# power_usb.net
KiCad netlist of a schematic drawn in Altium Designer
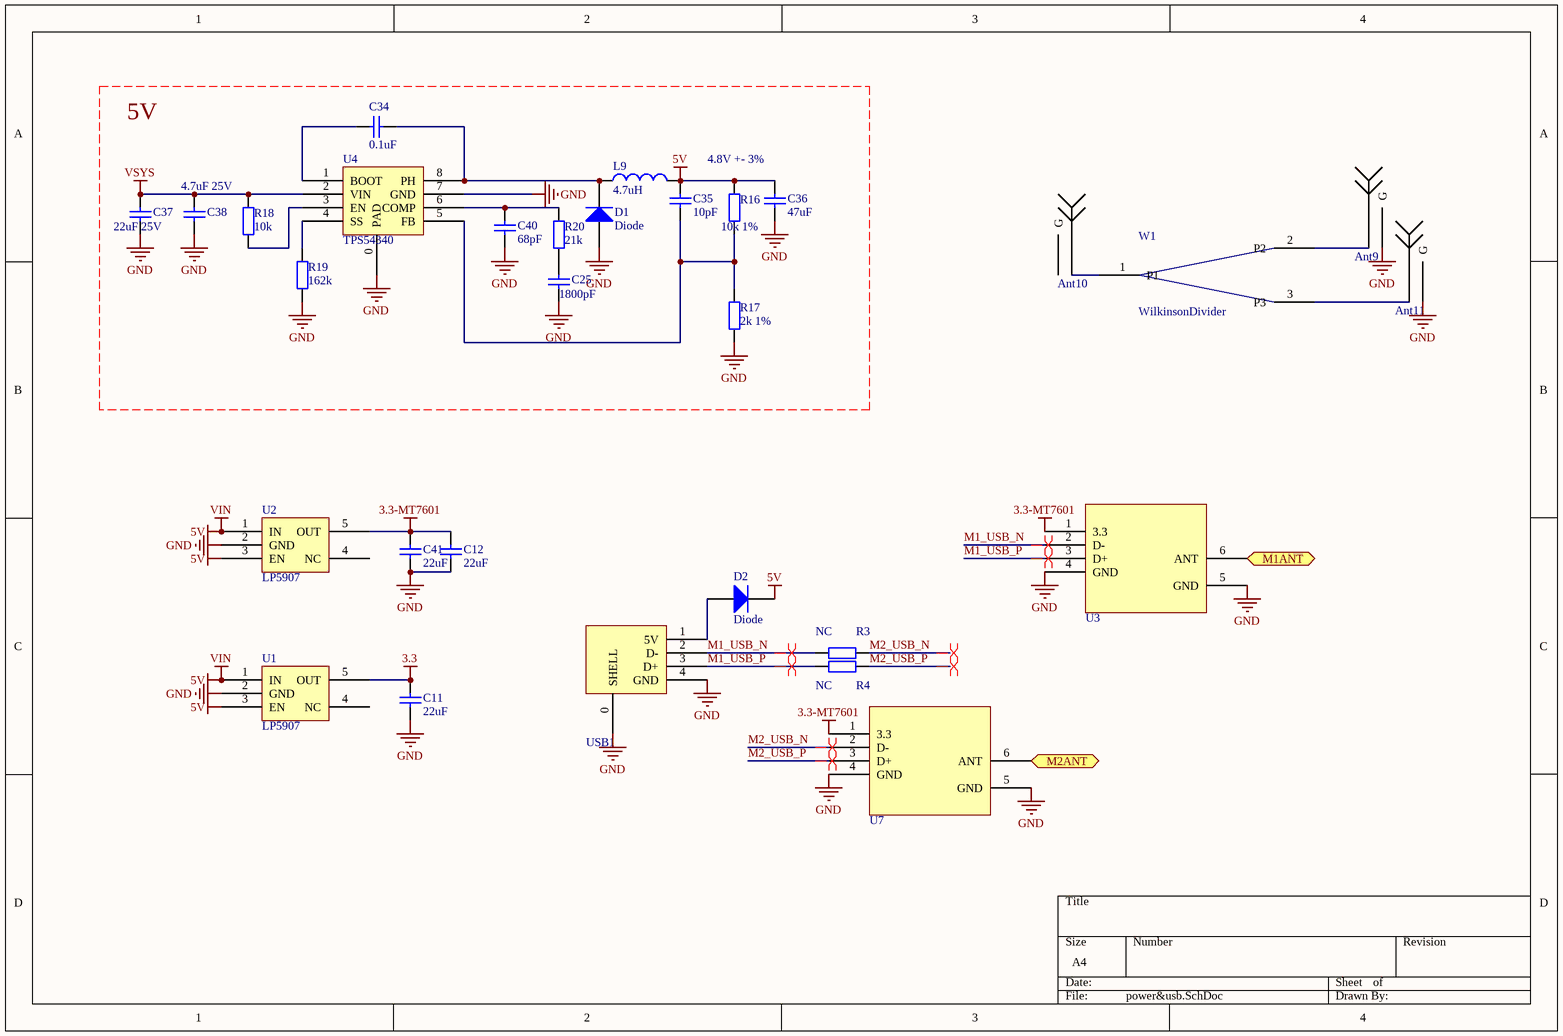
[diagram p0: power&usb.SchDoc]

(export (version "E")
  (design (tool "Eeschema 10.0.6"))
  (components
    (comp (ref "Ant9") (value "Antenna") (footprint "SMA-2") (libsource (lib "RTC6705") (part "Antenna")))
    (comp (ref "Ant10") (value "Antenna") (footprint "SMA-2") (libsource (lib "RTC6705") (part "Antenna")))
    (comp (ref "Ant11") (value "Antenna") (footprint "SMA-2") (libsource (lib "RTC6705") (part "Antenna")))
    (comp (ref "C11")
      (value "22uF")
      (footprint "0805")
      (description "Capacitor")
      (fields (field (name "Comment") "Cap") (field (name "PUBLISHER") "Altium Limited"))
      (libsource (lib "RTC6705") (part "Cap"))
    )
    (comp (ref "C12")
      (value "22uF")
      (footprint "0805")
      (description "Capacitor")
      (fields (field (name "Comment") "Cap") (field (name "PUBLISHER") "Altium Limited"))
      (libsource (lib "RTC6705") (part "Cap"))
    )
    (comp (ref "C25")
      (value "1800pF")
      (footprint "0402")
      (description "Capacitor")
      (fields (field (name "Comment") "Cap") (field (name "PUBLISHER") "Altium Limited"))
      (libsource (lib "RTC6705") (part "Cap"))
    )
    (comp (ref "C34")
      (value "0.1uF")
      (footprint "0402")
      (description "Capacitor")
      (fields (field (name "Comment") "Cap") (field (name "PUBLISHER") "Altium Limited"))
      (libsource (lib "RTC6705") (part "Cap"))
    )
    (comp (ref "C35")
      (value "10pF")
      (footprint "0402")
      (description "Capacitor")
      (fields (field (name "Comment") "Cap") (field (name "PUBLISHER") "Altium Limited"))
      (libsource (lib "RTC6705") (part "Cap"))
    )
    (comp (ref "C36")
      (value "47uF")
      (footprint "1210")
      (description "Capacitor")
      (fields (field (name "Comment") "Cap") (field (name "PUBLISHER") "Altium Limited"))
      (libsource (lib "RTC6705") (part "Cap"))
    )
    (comp (ref "C37")
      (value "22uF 25V")
      (footprint "1210")
      (description "Capacitor")
      (fields (field (name "Comment") "Cap") (field (name "PUBLISHER") "Altium Limited"))
      (libsource (lib "RTC6705") (part "Cap"))
    )
    (comp (ref "C38")
      (value "4.7uF 25V")
      (footprint "0805")
      (description "Capacitor")
      (fields (field (name "Comment") "Cap") (field (name "PUBLISHER") "Altium Limited"))
      (libsource (lib "RTC6705") (part "Cap"))
    )
    (comp (ref "C40")
      (value "68pF")
      (footprint "0402")
      (description "Capacitor")
      (fields (field (name "Comment") "Cap") (field (name "PUBLISHER") "Altium Limited"))
      (libsource (lib "RTC6705") (part "Cap"))
    )
    (comp (ref "C41")
      (value "22uF")
      (footprint "0805")
      (description "Capacitor")
      (fields (field (name "Comment") "Cap") (field (name "PUBLISHER") "Altium Limited"))
      (libsource (lib "RTC6705") (part "Cap"))
    )
    (comp (ref "D1")
      (value "Diode")
      (footprint "LC-SMB(DO-214AA)_S1")
      (description "Default Diode")
      (fields (field (name "PUBLISHER") "Altium Limited"))
      (libsource (lib "Miscellaneous Devices") (part "Diode"))
    )
    (comp (ref "D2")
      (value "Diode")
      (footprint "0805")
      (description "Default Diode")
      (fields (field (name "PUBLISHER") "Altium Limited"))
      (libsource (lib "Miscellaneous Devices") (part "Diode"))
    )
    (comp (ref "L9")
      (value "4.7uH")
      (footprint "L7022")
      (description "Inductor")
      (fields (field (name "PUBLISHER") "Altium Limited"))
      (libsource (lib "Miscellaneous Devices") (part "Inductor"))
    )
    (comp (ref "R3")
      (value "NC")
      (footprint "0402")
      (description "Resistor")
      (fields (field (name "Comment") "Res2") (field (name "PUBLISHER") "Altium Limited"))
      (libsource (lib "") (part "Res2_1"))
    )
    (comp (ref "R4")
      (value "NC")
      (footprint "0402")
      (description "Resistor")
      (fields (field (name "Comment") "Res2") (field (name "PUBLISHER") "Altium Limited"))
      (libsource (lib "") (part "Res2_1"))
    )
    (comp (ref "R16")
      (value "10k 1%")
      (footprint "0402")
      (description "Resistor")
      (fields (field (name "Comment") "Res2") (field (name "PUBLISHER") "Altium Limited"))
      (libsource (lib "RTC6705") (part "Res2"))
    )
    (comp (ref "R17")
      (value "2k 1%")
      (footprint "0402")
      (description "Resistor")
      (fields (field (name "Comment") "Res2") (field (name "PUBLISHER") "Altium Limited"))
      (libsource (lib "RTC6705") (part "Res2"))
    )
    (comp (ref "R18")
      (value "10k")
      (footprint "0402")
      (description "Resistor")
      (fields (field (name "Comment") "Res2") (field (name "PUBLISHER") "Altium Limited"))
      (libsource (lib "RTC6705") (part "Res2"))
    )
    (comp (ref "R19")
      (value "162k")
      (footprint "0402")
      (description "Resistor")
      (fields (field (name "Comment") "Res2") (field (name "PUBLISHER") "Altium Limited"))
      (libsource (lib "RTC6705") (part "Res2"))
    )
    (comp (ref "R20")
      (value "21k")
      (footprint "0402")
      (description "Resistor")
      (fields (field (name "Comment") "Res2") (field (name "PUBLISHER") "Altium Limited"))
      (libsource (lib "RTC6705") (part "Res2"))
    )
    (comp (ref "U1") (value "LP5907") (footprint "SOT23-5") (libsource (lib "RTC6705") (part "LP5907")))
    (comp (ref "U2") (value "LP5907") (footprint "SOT23-5") (libsource (lib "RTC6705") (part "LP5907")))
    (comp (ref "U3")
      (value "MT7601-Module")
      (footprint "MT7601-Module")
      (libsource (lib "WifiGain") (part "MT7601-Module"))
    )
    (comp (ref "U4") (value "TPS54340") (footprint "D8-Pad") (libsource (lib "sch") (part "TPS54340")))
    (comp (ref "U7")
      (value "MT7601-Module")
      (footprint "MT7601-Module")
      (libsource (lib "WifiGain") (part "MT7601-Module"))
    )
    (comp (ref "USB1") (value "USB-A") (footprint "USB-A-Male") (libsource (lib "WifiGain") (part "USB-A")))
    (comp (ref "W1")
      (value "WilkinsonDivider")
      (footprint "WilkinsonDivider")
      (libsource (lib "WifiGain") (part "WilkinsonDivider"))
    )
  )
  (nets
    (net (code "1") (name "/M1ANT") (class "Default")
      (node (ref "U3") (pin "6") (pinfunction "ANT_6") (pintype "passive"))
    )
    (net (code "2") (name "/M1_USB_N") (class "Default")
      (node (ref "R3") (pin "2") (pinfunction "2_2") (pintype "passive"))
      (node (ref "U3") (pin "2") (pinfunction "D-_2") (pintype "passive"))
      (node (ref "USB1") (pin "2") (pinfunction "D-_2") (pintype "passive"))
    )
    (net (code "3") (name "/M1_USB_P") (class "Default")
      (node (ref "R4") (pin "2") (pinfunction "2_2") (pintype "passive"))
      (node (ref "U3") (pin "3") (pinfunction "D+_3") (pintype "passive"))
      (node (ref "USB1") (pin "3") (pinfunction "D+_3") (pintype "passive"))
    )
    (net (code "4") (name "/M2ANT") (class "Default")
      (node (ref "U7") (pin "6") (pinfunction "ANT_6") (pintype "passive"))
    )
    (net (code "5") (name "/M2_USB_N") (class "Default")
      (node (ref "R3") (pin "1") (pinfunction "1_1") (pintype "passive"))
      (node (ref "U7") (pin "2") (pinfunction "D-_2") (pintype "passive"))
    )
    (net (code "6") (name "/M2_USB_P") (class "Default")
      (node (ref "R4") (pin "1") (pinfunction "1_1") (pintype "passive"))
      (node (ref "U7") (pin "3") (pinfunction "D+_3") (pintype "passive"))
    )
    (net (code "7") (name "3.3") (class "Default")
      (node (ref "C11") (pin "2") (pinfunction "2_2") (pintype "passive"))
      (node (ref "U1") (pin "5") (pinfunction "OUT_5") (pintype "passive"))
    )
    (net (code "8") (name "3.3-MT7601") (class "Default")
      (node (ref "C12") (pin "2") (pinfunction "2_2") (pintype "passive"))
      (node (ref "C41") (pin "2") (pinfunction "2_2") (pintype "passive"))
      (node (ref "U2") (pin "5") (pinfunction "OUT_5") (pintype "passive"))
      (node (ref "U3") (pin "1") (pinfunction "3.3_1") (pintype "passive"))
      (node (ref "U7") (pin "1") (pinfunction "3.3_1") (pintype "passive"))
    )
    (net (code "9") (name "5V") (class "Default")
      (node (ref "C35") (pin "1") (pinfunction "1_1") (pintype "passive"))
      (node (ref "C36") (pin "1") (pinfunction "1_1") (pintype "passive"))
      (node (ref "D2") (pin "2") (pinfunction "K_2") (pintype "passive"))
      (node (ref "L9") (pin "2") (pinfunction "2_2") (pintype "passive"))
      (node (ref "R16") (pin "1") (pinfunction "1_1") (pintype "passive"))
      (node (ref "U1") (pin "1") (pinfunction "IN_1") (pintype "passive"))
      (node (ref "U1") (pin "3") (pinfunction "EN_3") (pintype "passive"))
      (node (ref "U2") (pin "1") (pinfunction "IN_1") (pintype "passive"))
      (node (ref "U2") (pin "3") (pinfunction "EN_3") (pintype "passive"))
    )
    (net (code "10") (name "GND") (class "Default")
      (node (ref "Ant11") (pin "GND") (pinfunction "G_GND") (pintype "passive"))
      (node (ref "Ant9") (pin "GND") (pinfunction "G_GND") (pintype "passive"))
      (node (ref "C11") (pin "1") (pinfunction "1_1") (pintype "passive"))
      (node (ref "C12") (pin "1") (pinfunction "1_1") (pintype "passive"))
      (node (ref "C25") (pin "2") (pinfunction "2_2") (pintype "passive"))
      (node (ref "C36") (pin "2") (pinfunction "2_2") (pintype "passive"))
      (node (ref "C37") (pin "2") (pinfunction "2_2") (pintype "passive"))
      (node (ref "C38") (pin "2") (pinfunction "2_2") (pintype "passive"))
      (node (ref "C40") (pin "2") (pinfunction "2_2") (pintype "passive"))
      (node (ref "C41") (pin "1") (pinfunction "1_1") (pintype "passive"))
      (node (ref "D1") (pin "1") (pinfunction "A_1") (pintype "passive"))
      (node (ref "R17") (pin "2") (pinfunction "2_2") (pintype "passive"))
      (node (ref "R19") (pin "2") (pinfunction "2_2") (pintype "passive"))
      (node (ref "U1") (pin "2") (pinfunction "GND_2") (pintype "passive"))
      (node (ref "U2") (pin "2") (pinfunction "GND_2") (pintype "passive"))
      (node (ref "U3") (pin "4") (pinfunction "GND_4") (pintype "passive"))
      (node (ref "U3") (pin "5") (pinfunction "GND_5") (pintype "passive"))
      (node (ref "U4") (pin "0") (pinfunction "PAD_0") (pintype "passive"))
      (node (ref "U4") (pin "7") (pinfunction "GND_7") (pintype "passive"))
      (node (ref "U7") (pin "4") (pinfunction "GND_4") (pintype "passive"))
      (node (ref "U7") (pin "5") (pinfunction "GND_5") (pintype "passive"))
      (node (ref "USB1") (pin "0") (pinfunction "SHELL_0") (pintype "passive"))
      (node (ref "USB1") (pin "4") (pinfunction "GND_4") (pintype "passive"))
    )
    (net (code "11") (name "Net-(C25-Pad1)") (class "Default")
      (node (ref "C25") (pin "1") (pinfunction "1_1") (pintype "passive"))
      (node (ref "R20") (pin "2") (pinfunction "2_2") (pintype "passive"))
    )
    (net (code "12") (name "Net-(D1-K)") (class "Default")
      (node (ref "C34") (pin "1") (pinfunction "1_1") (pintype "passive"))
      (node (ref "D1") (pin "2") (pinfunction "K_2") (pintype "passive"))
      (node (ref "L9") (pin "1") (pinfunction "1_1") (pintype "passive"))
      (node (ref "U4") (pin "8") (pinfunction "PH_8") (pintype "passive"))
    )
    (net (code "13") (name "Net-(D2-A)") (class "Default")
      (node (ref "D2") (pin "1") (pinfunction "A_1") (pintype "passive"))
      (node (ref "USB1") (pin "1") (pinfunction "5V_1") (pintype "passive"))
    )
    (net (code "14") (name "Net-(U4-BOOT)") (class "Default")
      (node (ref "C34") (pin "2") (pinfunction "2_2") (pintype "passive"))
      (node (ref "U4") (pin "1") (pinfunction "BOOT_1") (pintype "passive"))
    )
    (net (code "15") (name "Net-(U4-COMP)") (class "Default")
      (node (ref "C40") (pin "1") (pinfunction "1_1") (pintype "passive"))
      (node (ref "R20") (pin "1") (pinfunction "1_1") (pintype "passive"))
      (node (ref "U4") (pin "6") (pinfunction "COMP_6") (pintype "passive"))
    )
    (net (code "16") (name "Net-(U4-EN)") (class "Default")
      (node (ref "R18") (pin "2") (pinfunction "2_2") (pintype "passive"))
      (node (ref "U4") (pin "3") (pinfunction "EN_3") (pintype "passive"))
    )
    (net (code "17") (name "Net-(U4-FB)") (class "Default")
      (node (ref "C35") (pin "2") (pinfunction "2_2") (pintype "passive"))
      (node (ref "R16") (pin "2") (pinfunction "2_2") (pintype "passive"))
      (node (ref "R17") (pin "1") (pinfunction "1_1") (pintype "passive"))
      (node (ref "U4") (pin "5") (pinfunction "FB_5") (pintype "passive"))
    )
    (net (code "18") (name "Net-(U4-SS)") (class "Default")
      (node (ref "R19") (pin "1") (pinfunction "1_1") (pintype "passive"))
      (node (ref "U4") (pin "4") (pinfunction "SS_4") (pintype "passive"))
    )
    (net (code "19") (name "Net-(W1-P1)") (class "Default")
      (node (ref "Ant10") (pin "1") (pinfunction "1_1") (pintype "passive"))
      (node (ref "W1") (pin "1") (pinfunction "P1_1") (pintype "passive"))
    )
    (net (code "20") (name "Net-(W1-P2)") (class "Default")
      (node (ref "Ant9") (pin "1") (pinfunction "1_1") (pintype "passive"))
      (node (ref "W1") (pin "2") (pinfunction "P2_2") (pintype "passive"))
    )
    (net (code "21") (name "Net-(W1-P3)") (class "Default")
      (node (ref "Ant11") (pin "1") (pinfunction "1_1") (pintype "passive"))
      (node (ref "W1") (pin "3") (pinfunction "P3_3") (pintype "passive"))
    )
    (net (code "22") (name "VSYS") (class "Default")
      (node (ref "C37") (pin "1") (pinfunction "1_1") (pintype "passive"))
      (node (ref "C38") (pin "1") (pinfunction "1_1") (pintype "passive"))
      (node (ref "R18") (pin "1") (pinfunction "1_1") (pintype "passive"))
      (node (ref "U4") (pin "2") (pinfunction "VIN_2") (pintype "passive"))
    )
    (net (code "23") (name "unconnected-(Ant10-G-PadGND)") (class "Default")
      (node (ref "Ant10") (pin "GND") (pinfunction "G_GND") (pintype "passive"))
    )
    (net (code "24") (name "unconnected-(U1-NC-Pad4)") (class "Default")
      (node (ref "U1") (pin "4") (pinfunction "NC_4") (pintype "passive"))
    )
    (net (code "25") (name "unconnected-(U2-NC-Pad4)") (class "Default")
      (node (ref "U2") (pin "4") (pinfunction "NC_4") (pintype "passive"))
    )
  )
)
